# POWER_BLOCK.net
KiCad netlist of a schematic drawn in Altium Designer
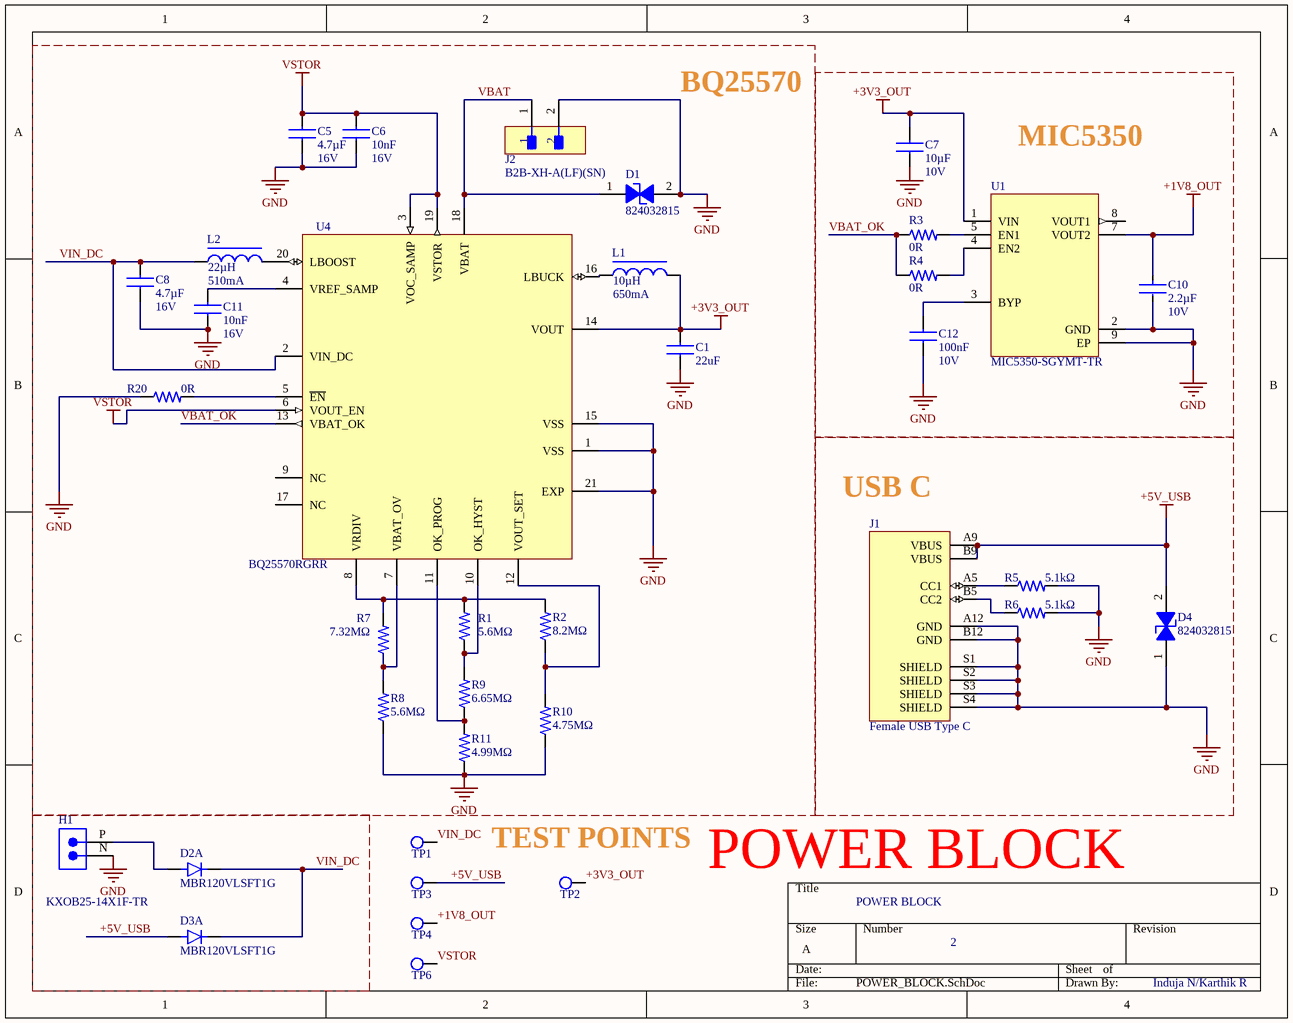
[diagram p0: POWER_BLOCK.SchDoc]

(export (version "E")
  (design (tool "Eeschema 10.0.6"))
  (components
    (comp (ref "C1")
      (value "22uF")
      (footprint "Capacitor 0603")
      (description "CAP CER 22UF 10V X5R 0603")
      (fields
        (field (name "MANUFACTURER") "Murata")
        (field (name "MANUFACTURER PART NUMBER") "GRM188R61A226ME15D")
      )
      (libsource (lib "LPEDT_Components") (part "GRM188R61A226ME15D"))
    )
    (comp (ref "C5")
      (value "4.7µF")
      (footprint "Capacitor 0603")
      (description "16V 4.7uF X7R ±10% 0603 Multilayer Ceramic Capacitors MLCC - SMD/SMT ROHS")
      (fields
        (field (name "MANUFACTURER") "Murata")
        (field (name "MANUFACTURER PART NUMBER") "GRM188Z71C475KE21D")
        (field (name "VOLTAGE RATING (DC)") "16V")
      )
      (libsource (lib "LPEDT_Components") (part "CAP 4.7uF 16V X7R"))
    )
    (comp (ref "C6")
      (value "10nF")
      (footprint "Capacitor 0603")
      (description "Multilayer Ceramic Capacitors MLCC - SMD/SMT 16V 0.01uF X7R 0603 10% AEC-Q200")
      (fields
        (field (name "MANUFACTURER") "KEMET")
        (field (name "MANUFACTURER PART NUMBER") "C0603C103K4RECAUTO")
        (field (name "VOLTAGE RATING (DC)") "16V")
      )
      (libsource (lib "LPEDT_Components") (part "CAP 10nF 0603"))
    )
    (comp (ref "C7")
      (value "10µF")
      (footprint "CAP_0603_1MM")
      (description "10V 10uF X7R ±10% 0603 Multilayer Ceramic Capacitors MLCC - SMD/SMT ROHS")
      (fields
        (field (name "MANUFACTURER") "Murata")
        (field (name "MANUFACTURER PART NUMBER") "GRM188Z71A106KA73D")
        (field (name "VOLTAGE RATING") "10V")
      )
      (libsource (lib "LPEDT_Components") (part "CAP 10uF 0603"))
    )
    (comp (ref "C8")
      (value "4.7µF")
      (footprint "Capacitor 0603")
      (description "16V 4.7uF X7R ±10% 0603 Multilayer Ceramic Capacitors MLCC - SMD/SMT ROHS")
      (fields
        (field (name "MANUFACTURER") "Murata")
        (field (name "MANUFACTURER PART NUMBER") "GRM188Z71C475KE21D")
        (field (name "VOLTAGE RATING (DC)") "16V")
      )
      (libsource (lib "LPEDT_Components") (part "CAP 4.7uF 16V X7R"))
    )
    (comp (ref "C10")
      (value "2.2µF")
      (footprint "CAP_0603_1MM")
      (description "10V 2.2uF X7R ±10% 0603 Multilayer Ceramic Capacitors MLCC - SMD/SMT ROHS")
      (fields
        (field (name "MANUFACTURER") "Samsung Electro-Mechanics")
        (field (name "MANUFACTURER PART NUMBER") "CL10B225KP8NNNC")
        (field (name "VOLTAGE RATING (DC)") "10V")
      )
      (libsource (lib "LPEDT_Components") (part "CAP 2.2uF 0603"))
    )
    (comp (ref "C11")
      (value "10nF")
      (footprint "Capacitor 0603")
      (description "Multilayer Ceramic Capacitors MLCC - SMD/SMT 16V 0.01uF X7R 0603 10% AEC-Q200")
      (fields
        (field (name "MANUFACTURER") "KEMET")
        (field (name "MANUFACTURER PART NUMBER") "C0603C103K4RECAUTO")
        (field (name "VOLTAGE RATING (DC)") "16V")
      )
      (libsource (lib "LPEDT_Components") (part "CAP 10nF 0603"))
    )
    (comp (ref "C12")
      (value "100nF")
      (footprint "CAP_0603_1MM")
      (description "0603 0.1 uF 10 V ±10% Tolerance X7R SMT Multilayer Ceramic Chip Capacitor")
      (fields
        (field (name "MANUFACTURER") "Vishay")
        (field (name "MANUFACTURER PART NUMBER") "VJ0603Y104KXQCW1BC")
        (field (name "VOLTAGE RATING (DC)") "10V")
      )
      (libsource (lib "LPEDT_Components") (part "CAP 0.1uF 0603"))
    )
    (comp (ref "D1")
      (value "824032815")
      (footprint "WE-TVS_DFN1610-2L")
      (description "824032815 Tvs Diode, Bidir, 5V, Dfn1610 Rohs Compliant: Yes ¦Wurth Elektronik 824032815")
      (libsource (lib "LPEDT_Components") (part "TVS Diode ESD Protection"))
    )
    (comp (ref "D2")
      (value "MBR120VLSFT1G")
      (footprint "ONSC-SOD-123FL-2-498-01_V")
      (description "Schottky Power Rectifier, 2-Pin SOD-123, Pb-Free, Tape and Reel")
      (fields (field (name "MANUFACTURER") "On Semiconductor"))
      (libsource (lib "LPEDT_Components") (part "Diode Schottky"))
    )
    (comp (ref "D3")
      (value "MBR120VLSFT1G")
      (footprint "ONSC-SOD-123FL-2-498-01_V")
      (description "Schottky Power Rectifier, 2-Pin SOD-123, Pb-Free, Tape and Reel")
      (fields (field (name "MANUFACTURER") "On Semiconductor"))
      (libsource (lib "LPEDT_Components") (part "Diode Schottky"))
    )
    (comp (ref "D4")
      (value "824032815")
      (footprint "WE-TVS_DFN1610-2L")
      (description "824032815 Tvs Diode, Bidir, 5V, Dfn1610 Rohs Compliant: Yes ¦Wurth Elektronik 824032815")
      (libsource (lib "LPEDT_Components") (part "TVS Diode ESD Protection"))
    )
    (comp (ref "H1")
      (value "KXOB25-14X1F-TR")
      (footprint "SOLAR CELL")
      (description "MONOCRYS SOLAR CELL 30.7MW 690MV")
      (fields
        (field (name "MANUFACTURER") "Sullins")
        (field (name "MANUFACTURER PART NUMBER") "PRPC002SAAN-RC")
      )
      (libsource (lib "LPEDT_Components") (part "SOLAR_CELL"))
    )
    (comp (ref "J1")
      (value "Female USB Type C")
      (footprint "GCT_USB4125-GF-A_REVA2")
      (fields (field (name "MANUFACTURER PART NUMBER") "USB4125-GF-A_REVA2"))
      (libsource (lib "LPEDT_Components") (part "USB-C Power Connector"))
    )
    (comp (ref "J2")
      (value "B2B-XH-A(LF)(SN)")
      (footprint "FP-B2B-XH-A_LF_SN-MFG")
      (description "CONN HEADER VERT 2POS 2.5MM")
      (libsource (lib "LPEDT_Components") (part "CMP-2000-05888-3"))
    )
    (comp (ref "L1")
      (value "744029100")
      (footprint "WE-TPC_2813")
      (description "10 µH Shielded Drum Core, Wirewound Inductor 650 mA 470mOhm Max Nonstandard")
      (fields
        (field (name "TOLERANCE") "30%")
        (field (name "INDUCTANCE") "10µH")
        (field (name "CURRENT RATING") "650mA")
      )
      (libsource (lib "LPEDT_Components") (part "CMP-0227-00077-3"))
    )
    (comp (ref "L2")
      (value "744031220")
      (footprint "WE-TPC_3816")
      (description "22 µH Shielded Drum Core, Wirewound Inductor 510 mA 450mOhm Max Nonstandard")
      (fields
        (field (name "CURRENT RATING") "510mA")
        (field (name "TOLERANCE") "30%")
        (field (name "INDUCTANCE") "22µH")
      )
      (libsource (lib "LPEDT_Components") (part "CMP-0227-00346-4"))
    )
    (comp (ref "R1")
      (value "5.6MΩ")
      (footprint "RES_0603_1608X06")
      (description "1.24 MOhms ±1% 0.125W, 1/8W Chip Resistor 0603 (1608 Metric) Automotive AEC-Q200 Thick Film")
      (fields
        (field (name "MANUFACTURER") "Yageo")
        (field (name "MANUFACTURER PART NUMBER") "RC0603JR-075M6L")
      )
      (libsource (lib "LPEDT_Components") (part "RES 1.24M 0603"))
    )
    (comp (ref "R2")
      (value "8.2MΩ")
      (footprint "RES_0603_1608X06")
      (fields
        (field (name "MANUFACTURER") "Yageo")
        (field (name "MANUFACTURER PART NUMBER") "RC0603JR-078M2L")
        (field (name "TOLERANCE") "5%")
      )
      (libsource (lib "LPEDT_Components") (part "RES 8.2M 0603"))
    )
    (comp (ref "R3")
      (value "0R")
      (footprint "RES_0603_1608X06")
      (description "GENERAL PURPOSE CHIP RESISTOR Metal Glaze/thick Film, 0.1W, 0ohm, Surface Mount, 0603")
      (fields
        (field (name "MANUFACTURER") "Yageo Group")
        (field (name "MANUFACTURER PART NUMBER") "RC0603JR-070RL")
      )
      (libsource (lib "LPEDT_Components") (part "RES 0R 0603"))
    )
    (comp (ref "R4")
      (value "0R")
      (footprint "RES_0603_1608X06")
      (description "GENERAL PURPOSE CHIP RESISTOR Metal Glaze/thick Film, 0.1W, 0ohm, Surface Mount, 0603")
      (fields
        (field (name "MANUFACTURER") "Yageo Group")
        (field (name "MANUFACTURER PART NUMBER") "RC0603JR-070RL")
      )
      (libsource (lib "LPEDT_Components") (part "RES 0R 0603"))
    )
    (comp (ref "R5")
      (value "5.1kΩ")
      (footprint "RES_0603_1608X06")
      (fields
        (field (name "MANUFACTURER") "Yageo")
        (field (name "MANUFACTURER PART NUMBER") "RC0603FR-075K1L")
        (field (name "TOLERANCE") "1%")
      )
      (libsource (lib "LPEDT_Components") (part "RES 5.1K 0603"))
    )
    (comp (ref "R6")
      (value "5.1kΩ")
      (footprint "RES_0603_1608X06")
      (fields
        (field (name "MANUFACTURER") "Yageo")
        (field (name "MANUFACTURER PART NUMBER") "RC0603FR-075K1L")
        (field (name "TOLERANCE") "1%")
      )
      (libsource (lib "LPEDT_Components") (part "RES 5.1K 0603"))
    )
    (comp (ref "R7")
      (value "7.32MΩ")
      (footprint "RES_0603_1608X06")
      (fields
        (field (name "MANUFACTURER") "Yageo")
        (field (name "MANUFACTURER PART NUMBER") "RC0402FR-077M32L")
        (field (name "TOLERANCE") "1%")
      )
      (libsource (lib "LPEDT_Components") (part "RES 7.32M 0603"))
    )
    (comp (ref "R8")
      (value "5.6MΩ")
      (footprint "RES_0603_1608X06")
      (fields
        (field (name "MANUFACTURER") "Yageo")
        (field (name "MANUFACTURER PART NUMBER") "RC0603JR-075M6L")
        (field (name "TOLERANCE") "5%")
      )
      (libsource (lib "LPEDT_Components") (part "RES 5.62M 0603"))
    )
    (comp (ref "R9")
      (value "6.65MΩ")
      (footprint "RES_0603_1608X06")
      (description "Res Thick Film 0603 6.65M Ohm 1% 0.1W(1/10W) ±200ppm/C Pad SMD T/R Automotive AEC-Q200")
      (fields
        (field (name "MANUFACTURER") "Stackpole Electronics")
        (field (name "MANUFACTURER PART NUMBER") "RMCF0603FT6M65")
      )
      (libsource (lib "LPEDT_Components") (part "RES 6.65M 0603"))
    )
    (comp (ref "R10")
      (value "4.75MΩ")
      (footprint "RES_0603_1608X06")
      (fields
        (field (name "MANUFACTURER") "Yageo")
        (field (name "MANUFACTURER PART NUMBER") "RC0603FR-074M75L")
        (field (name "TOLERANCE") "1%")
      )
      (libsource (lib "LPEDT_Components") (part "RES 4.75M 0603"))
    )
    (comp (ref "R11")
      (value "4.99MΩ")
      (footprint "RES_0603_1608X06")
      (fields
        (field (name "MANUFACTURER") "Yageo")
        (field (name "MANUFACTURER PART NUMBER") "RC0603FR-074M99L")
        (field (name "TOLERANCE") "1%")
      )
      (libsource (lib "LPEDT_Components") (part "RES 4.99M 0603"))
    )
    (comp (ref "R20")
      (value "0R")
      (footprint "RES_0603_1608X06")
      (description "GENERAL PURPOSE CHIP RESISTOR Metal Glaze/thick Film, 0.1W, 0ohm, Surface Mount, 0603")
      (fields
        (field (name "MANUFACTURER") "Yageo Group")
        (field (name "MANUFACTURER PART NUMBER") "RC0603JR-070RL")
      )
      (libsource (lib "LPEDT_Components") (part "RES 0R 0603"))
    )
    (comp (ref "TP1")
      (value "Test Point")
      (footprint "Test Point")
      (libsource (lib "LPEDT_Components") (part "Test Point"))
    )
    (comp (ref "TP2")
      (value "Test Point")
      (footprint "Test Point")
      (libsource (lib "LPEDT_Components") (part "Test Point"))
    )
    (comp (ref "TP3")
      (value "Test Point")
      (footprint "Test Point")
      (libsource (lib "LPEDT_Components") (part "Test Point"))
    )
    (comp (ref "TP4")
      (value "Test Point")
      (footprint "Test Point")
      (libsource (lib "LPEDT_Components") (part "Test Point"))
    )
    (comp (ref "TP6")
      (value "Test Point")
      (footprint "Test Point")
      (libsource (lib "LPEDT_Components") (part "Test Point"))
    )
    (comp (ref "U1")
      (value "MIC5350-SGYMT-TR")
      (footprint "SON50P200X200X60-9N")
      (description "Linear Voltage Regulator IC Positive Fixed 2 Output 300mA, 500mA 8-TMLFÂ® (2x2)")
      (fields (field (name "MF") "Microchip"))
      (libsource (lib "LPEDT_Components") (part "MIC5350-SGYMT-TR"))
    )
    (comp (ref "U4")
      (value "BQ25570RGRR")
      (footprint "QFN50P350X350X100-21N")
      (description "Ultra Low power Harvester power Management IC with boost charger, and Nanopower Buck Converter")
      (fields (field (name "MF") "Texas Instruments"))
      (libsource (lib "LPEDT_Components") (part "BQ25570RGRR"))
    )
  )
  (nets
    (net (code "1") (name "+1V8_OUT") (class "Default")
      (node (ref "C10") (pin "1") (pinfunction "1_1") (pintype "passive"))
      (node (ref "TP4") (pin "1") (pinfunction "1_1") (pintype "passive"))
      (node (ref "U1") (pin "7") (pinfunction "VOUT2_7") (pintype "power_in"))
    )
    (net (code "2") (name "+3V3_OUT") (class "Default")
      (node (ref "C1") (pin "2") (pinfunction "2_2") (pintype "passive"))
      (node (ref "C7") (pin "1") (pinfunction "1_1") (pintype "passive"))
      (node (ref "L1") (pin "2") (pinfunction "2_2") (pintype "passive"))
      (node (ref "TP2") (pin "1") (pinfunction "1_1") (pintype "passive"))
      (node (ref "U1") (pin "1") (pinfunction "VIN_1") (pintype "power_in"))
      (node (ref "U4") (pin "14") (pinfunction "VOUT_14") (pintype "power_in"))
    )
    (net (code "3") (name "+5V_USB") (class "Default")
      (node (ref "D3") (pin "1") (pinfunction "1_1") (pintype "passive"))
      (node (ref "D4") (pin "2") (pinfunction "GND_2") (pintype "passive"))
      (node (ref "J1") (pin "A9") (pinfunction "VBUS_A9") (pintype "power_in"))
      (node (ref "TP3") (pin "1") (pinfunction "1_1") (pintype "passive"))
    )
    (net (code "5") (name "/VBAT") (class "Default")
      (node (ref "D1") (pin "1") (pinfunction "I/O_1_1") (pintype "passive"))
      (node (ref "J2") (pin "1") (pinfunction "1_1") (pintype "passive"))
      (node (ref "U4") (pin "18") (pinfunction "VBAT_18") (pintype "power_in"))
    )
    (net (code "6") (name "/VBAT_OK") (class "Default")
      (node (ref "R3") (pin "1") (pinfunction "1_1") (pintype "passive"))
      (node (ref "R4") (pin "1") (pinfunction "1_1") (pintype "passive"))
      (node (ref "U4") (pin "13") (pinfunction "VBAT_OK_13") (pintype "output"))
    )
    (net (code "7") (name "/VIN_DC") (class "Default")
      (node (ref "C8") (pin "1") (pinfunction "1_1") (pintype "passive"))
      (node (ref "D2") (pin "2") (pinfunction "2_2") (pintype "passive"))
      (node (ref "D3") (pin "2") (pinfunction "2_2") (pintype "passive"))
      (node (ref "L2") (pin "1") (pinfunction "1_1") (pintype "passive"))
      (node (ref "TP1") (pin "1") (pinfunction "1_1") (pintype "passive"))
      (node (ref "U4") (pin "2") (pinfunction "VIN_DC_2") (pintype "passive"))
    )
    (net (code "8") (name "GND") (class "Default")
      (node (ref "C1") (pin "1") (pinfunction "1_1") (pintype "passive"))
      (node (ref "C10") (pin "2") (pinfunction "2_2") (pintype "passive"))
      (node (ref "C11") (pin "2") (pinfunction "2_2") (pintype "passive"))
      (node (ref "C12") (pin "2") (pinfunction "2_2") (pintype "passive"))
      (node (ref "C5") (pin "2") (pinfunction "2_2") (pintype "passive"))
      (node (ref "C6") (pin "2") (pinfunction "2_2") (pintype "passive"))
      (node (ref "C7") (pin "2") (pinfunction "2_2") (pintype "passive"))
      (node (ref "C8") (pin "2") (pinfunction "2_2") (pintype "passive"))
      (node (ref "D1") (pin "2") (pinfunction "GND_2") (pintype "passive"))
      (node (ref "D4") (pin "1") (pinfunction "I/O_1_1") (pintype "passive"))
      (node (ref "H1") (pin "N") (pinfunction "2_N") (pintype "passive"))
      (node (ref "J1") (pin "A12") (pinfunction "GND_A12") (pintype "passive"))
      (node (ref "J1") (pin "B12") (pinfunction "GND_B12") (pintype "passive"))
      (node (ref "J1") (pin "S1") (pinfunction "SHIELD_S1") (pintype "passive"))
      (node (ref "J1") (pin "S2") (pinfunction "SHIELD_S2") (pintype "passive"))
      (node (ref "J1") (pin "S3") (pinfunction "SHIELD_S3") (pintype "passive"))
      (node (ref "J1") (pin "S4") (pinfunction "SHIELD_S4") (pintype "passive"))
      (node (ref "J2") (pin "2") (pinfunction "2_2") (pintype "passive"))
      (node (ref "R10") (pin "1") (pinfunction "1_1") (pintype "passive"))
      (node (ref "R11") (pin "1") (pinfunction "1_1") (pintype "passive"))
      (node (ref "R20") (pin "1") (pinfunction "1_1") (pintype "passive"))
      (node (ref "R5") (pin "2") (pinfunction "2_2") (pintype "passive"))
      (node (ref "R6") (pin "2") (pinfunction "2_2") (pintype "passive"))
      (node (ref "R8") (pin "1") (pinfunction "1_1") (pintype "passive"))
      (node (ref "U1") (pin "2") (pinfunction "GND_2") (pintype "passive"))
      (node (ref "U1") (pin "9") (pinfunction "EP_9") (pintype "passive"))
      (node (ref "U4") (pin "1") (pinfunction "VSS_1") (pintype "power_in"))
      (node (ref "U4") (pin "15") (pinfunction "VSS_15") (pintype "power_in"))
      (node (ref "U4") (pin "21") (pinfunction "EXP_21") (pintype "passive"))
    )
    (net (code "9") (name "Net-(H1-1)") (class "Default")
      (node (ref "D2") (pin "1") (pinfunction "1_1") (pintype "passive"))
      (node (ref "H1") (pin "P") (pinfunction "1_P") (pintype "power_in"))
    )
    (net (code "10") (name "Net-(J1-CC1)") (class "Default")
      (node (ref "J1") (pin "A5") (pinfunction "CC1_A5") (pintype "bidirectional"))
      (node (ref "R5") (pin "1") (pinfunction "1_1") (pintype "passive"))
    )
    (net (code "11") (name "Net-(J1-CC2)") (class "Default")
      (node (ref "J1") (pin "B5") (pinfunction "CC2_B5") (pintype "bidirectional"))
      (node (ref "R6") (pin "1") (pinfunction "1_1") (pintype "passive"))
    )
    (net (code "12") (name "Net-(U1-BYP)") (class "Default")
      (node (ref "C12") (pin "1") (pinfunction "1_1") (pintype "passive"))
      (node (ref "U1") (pin "3") (pinfunction "BYP_3") (pintype "passive"))
    )
    (net (code "13") (name "Net-(U1-EN1)") (class "Default")
      (node (ref "R3") (pin "2") (pinfunction "2_2") (pintype "passive"))
      (node (ref "U1") (pin "5") (pinfunction "EN1_5") (pintype "passive"))
    )
    (net (code "14") (name "Net-(U1-EN2)") (class "Default")
      (node (ref "R4") (pin "2") (pinfunction "2_2") (pintype "passive"))
      (node (ref "U1") (pin "4") (pinfunction "EN2_4") (pintype "passive"))
    )
    (net (code "15") (name "Net-(U4-LBOOST)") (class "Default")
      (node (ref "L2") (pin "2") (pinfunction "2_2") (pintype "passive"))
      (node (ref "U4") (pin "20") (pinfunction "LBOOST_20") (pintype "bidirectional"))
    )
    (net (code "16") (name "Net-(U4-LBUCK)") (class "Default")
      (node (ref "L1") (pin "1") (pinfunction "1_1") (pintype "passive"))
      (node (ref "U4") (pin "16") (pinfunction "LBUCK_16") (pintype "bidirectional"))
    )
    (net (code "17") (name "Net-(U4-OK_HYST)") (class "Default")
      (node (ref "R1") (pin "1") (pinfunction "1_1") (pintype "passive"))
      (node (ref "R9") (pin "2") (pinfunction "2_2") (pintype "passive"))
      (node (ref "U4") (pin "10") (pinfunction "OK_HYST_10") (pintype "passive"))
    )
    (net (code "18") (name "Net-(U4-OK_PROG)") (class "Default")
      (node (ref "R11") (pin "2") (pinfunction "2_2") (pintype "passive"))
      (node (ref "R9") (pin "1") (pinfunction "1_1") (pintype "passive"))
      (node (ref "U4") (pin "11") (pinfunction "OK_PROG_11") (pintype "passive"))
    )
    (net (code "19") (name "Net-(U4-VBAT_OV)") (class "Default")
      (node (ref "R7") (pin "1") (pinfunction "1_1") (pintype "passive"))
      (node (ref "R8") (pin "2") (pinfunction "2_2") (pintype "passive"))
      (node (ref "U4") (pin "7") (pinfunction "VBAT_OV_7") (pintype "passive"))
    )
    (net (code "20") (name "Net-(U4-VOUT_SET)") (class "Default")
      (node (ref "R10") (pin "2") (pinfunction "2_2") (pintype "passive"))
      (node (ref "R2") (pin "1") (pinfunction "1_1") (pintype "passive"))
      (node (ref "U4") (pin "12") (pinfunction "VOUT_SET_12") (pintype "passive"))
    )
    (net (code "21") (name "Net-(U4-VRDIV)") (class "Default")
      (node (ref "R1") (pin "2") (pinfunction "2_2") (pintype "passive"))
      (node (ref "R2") (pin "2") (pinfunction "2_2") (pintype "passive"))
      (node (ref "R7") (pin "2") (pinfunction "2_2") (pintype "passive"))
      (node (ref "U4") (pin "8") (pinfunction "VRDIV_8") (pintype "passive"))
    )
    (net (code "22") (name "Net-(U4-VREF_SAMP)") (class "Default")
      (node (ref "C11") (pin "1") (pinfunction "1_1") (pintype "passive"))
      (node (ref "U4") (pin "4") (pinfunction "VREF_SAMP_4") (pintype "passive"))
    )
    (net (code "23") (name "Net-(U4-~{EN})") (class "Default")
      (node (ref "R20") (pin "2") (pinfunction "2_2") (pintype "passive"))
      (node (ref "U4") (pin "5") (pinfunction "~{EN}_5") (pintype "passive"))
    )
    (net (code "24") (name "VSTOR") (class "Default")
      (node (ref "C5") (pin "1") (pinfunction "1_1") (pintype "passive"))
      (node (ref "C6") (pin "1") (pinfunction "1_1") (pintype "passive"))
      (node (ref "TP6") (pin "1") (pinfunction "1_1") (pintype "passive"))
      (node (ref "U4") (pin "19") (pinfunction "VSTOR_19") (pintype "output"))
      (node (ref "U4") (pin "3") (pinfunction "VOC_SAMP_3") (pintype "input"))
      (node (ref "U4") (pin "6") (pinfunction "VOUT_EN_6") (pintype "input"))
    )
    (net (code "25") (name "unconnected-(J1-VBUS-PadB9)") (class "Default")
      (node (ref "J1") (pin "B9") (pinfunction "VBUS_B9") (pintype "power_in"))
    )
    (net (code "26") (name "unconnected-(U1-VOUT1-Pad8)") (class "Default")
      (node (ref "U1") (pin "8") (pinfunction "VOUT1_8") (pintype "output"))
    )
    (net (code "27") (name "unconnected-(U4-NC-Pad9)") (class "Default")
      (node (ref "U4") (pin "9") (pinfunction "NC_9") (pintype "passive"))
    )
    (net (code "28") (name "unconnected-(U4-NC-Pad17)") (class "Default")
      (node (ref "U4") (pin "17") (pinfunction "NC_17") (pintype "passive"))
    )
  )
)
